# darlingtonDrivers.net
KiCad netlist of a schematic drawn in EAGLE
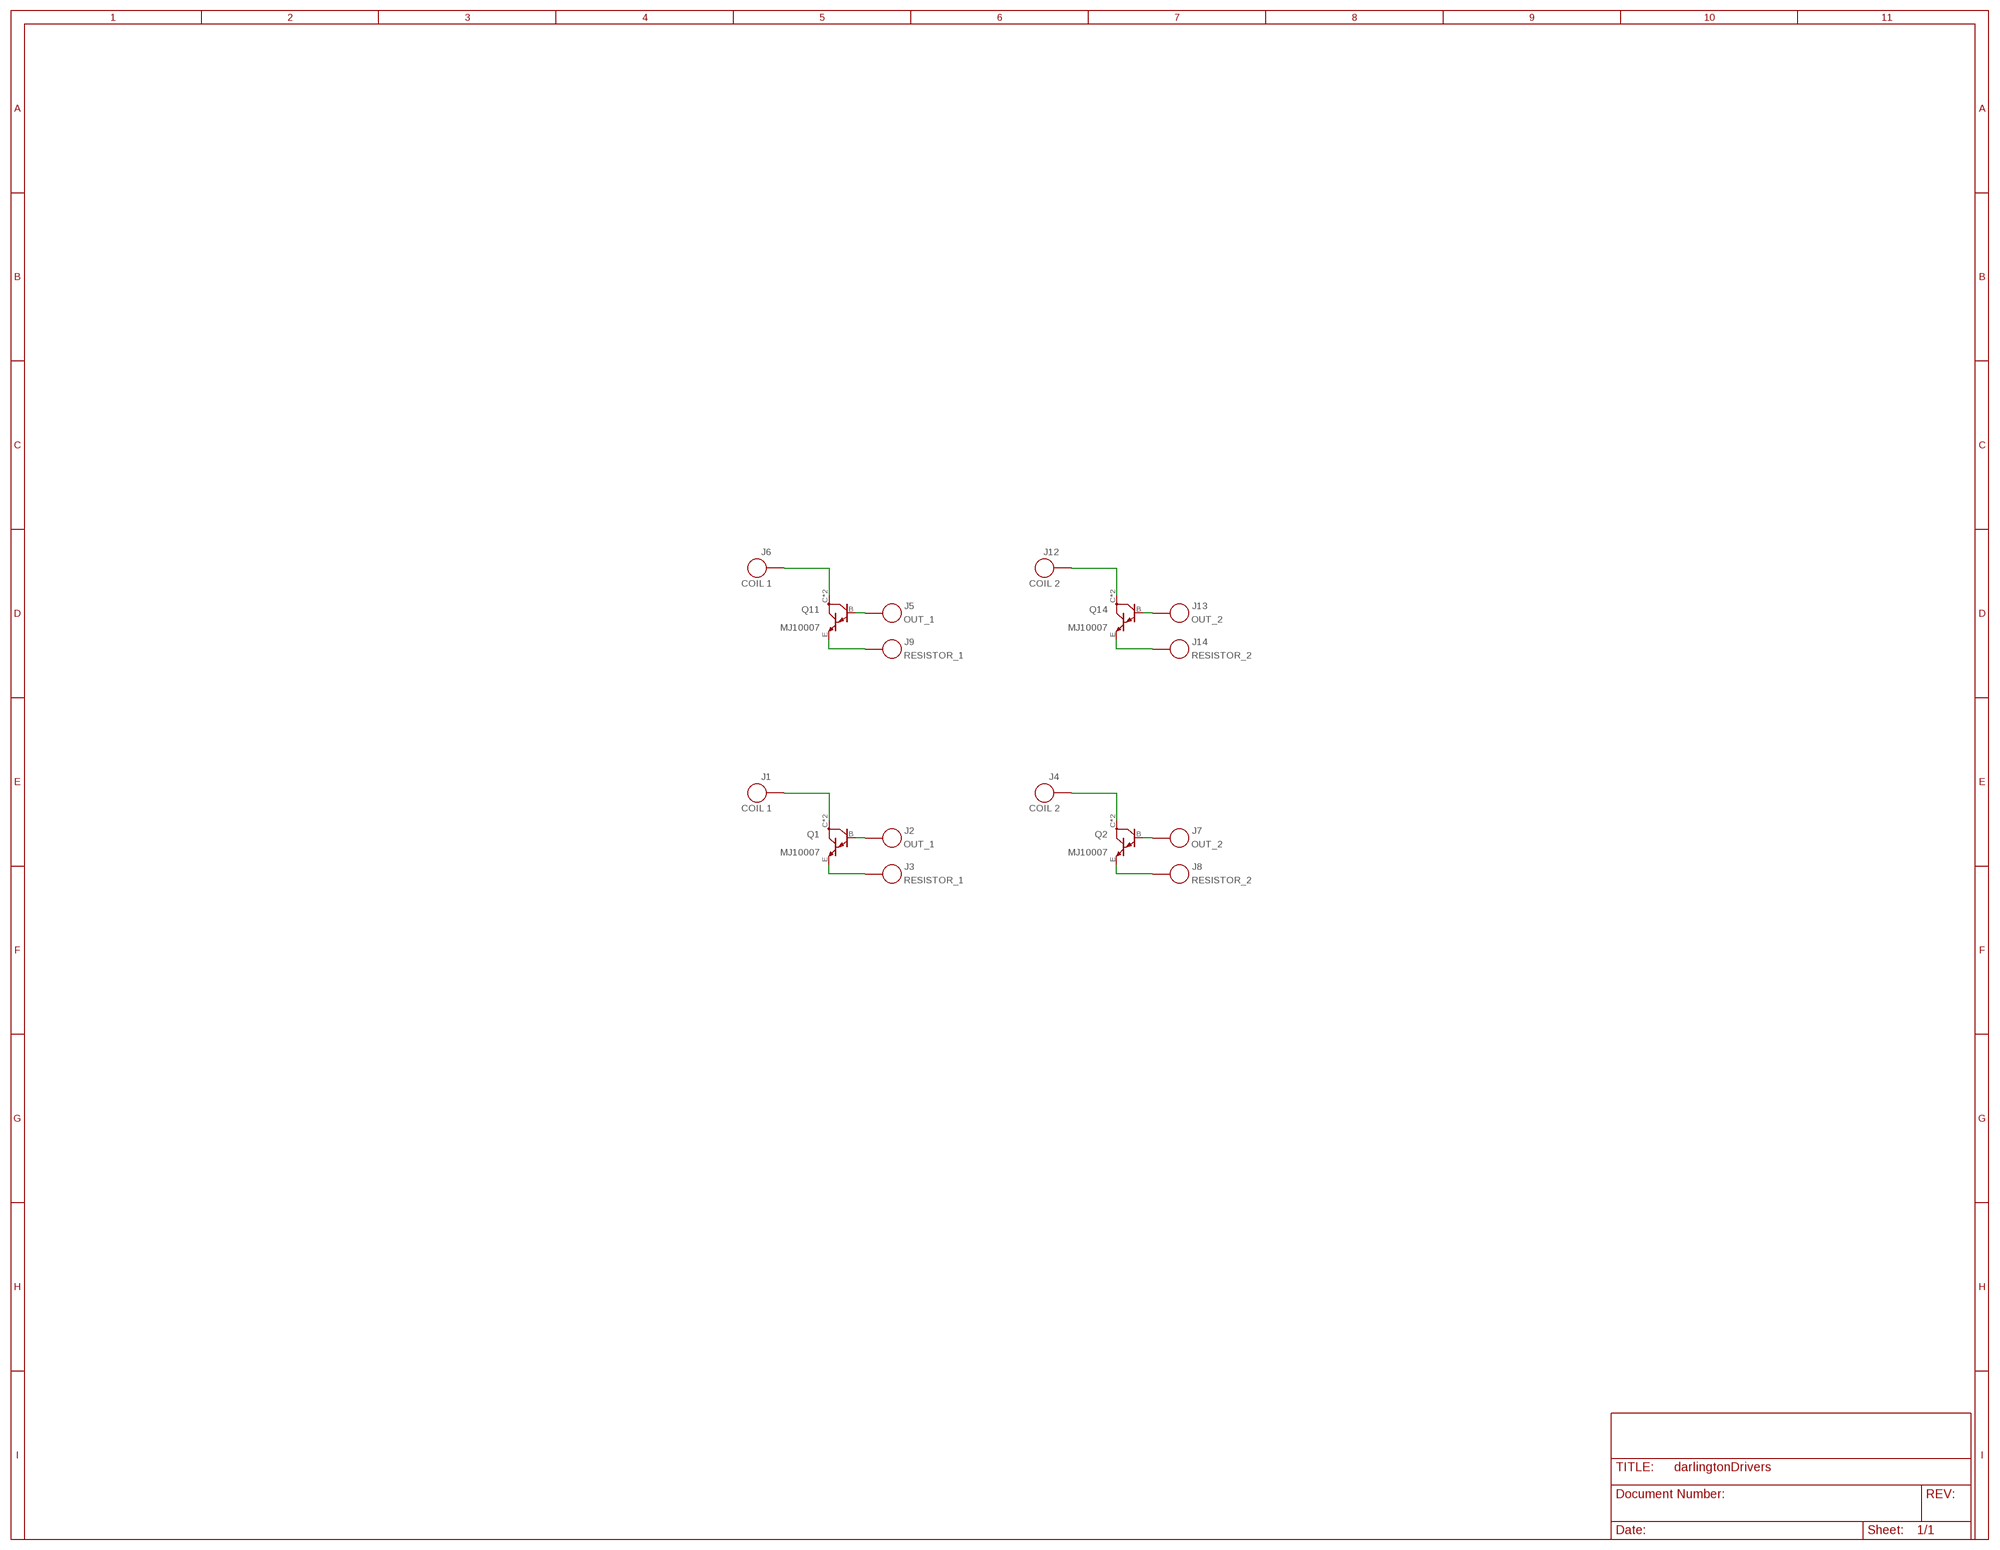
[diagram p0: schematic, sheet 1]

(export (version "E")
  (design (tool "Eeschema 10.0.6"))
  (components
    (comp (ref "J1")
      (value "COIL 1")
      (footprint "eagle-import:AWG18")
      (libsource (lib "eagle-import") (part "AWG18"))
    )
    (comp (ref "J2")
      (value "OUT_1")
      (footprint "eagle-import:AWG18")
      (libsource (lib "eagle-import") (part "AWG18"))
    )
    (comp (ref "J3")
      (value "RESISTOR_1")
      (footprint "eagle-import:AWG18")
      (libsource (lib "eagle-import") (part "AWG18"))
    )
    (comp (ref "J4")
      (value "COIL 2")
      (footprint "eagle-import:AWG18")
      (libsource (lib "eagle-import") (part "AWG18"))
    )
    (comp (ref "J5")
      (value "OUT_1")
      (footprint "eagle-import:AWG18")
      (libsource (lib "eagle-import") (part "AWG18"))
    )
    (comp (ref "J6")
      (value "COIL 1")
      (footprint "eagle-import:AWG18")
      (libsource (lib "eagle-import") (part "AWG18"))
    )
    (comp (ref "J7")
      (value "OUT_2")
      (footprint "eagle-import:AWG18")
      (libsource (lib "eagle-import") (part "AWG18"))
    )
    (comp (ref "J8")
      (value "RESISTOR_2")
      (footprint "eagle-import:AWG18")
      (libsource (lib "eagle-import") (part "AWG18"))
    )
    (comp (ref "J9")
      (value "RESISTOR_1")
      (footprint "eagle-import:AWG18")
      (libsource (lib "eagle-import") (part "AWG18"))
    )
    (comp (ref "J12")
      (value "COIL 2")
      (footprint "eagle-import:AWG18")
      (libsource (lib "eagle-import") (part "AWG18"))
    )
    (comp (ref "J13")
      (value "OUT_2")
      (footprint "eagle-import:AWG18")
      (libsource (lib "eagle-import") (part "AWG18"))
    )
    (comp (ref "J14")
      (value "RESISTOR_2")
      (footprint "eagle-import:AWG18")
      (libsource (lib "eagle-import") (part "AWG18"))
    )
    (comp (ref "Q1")
      (value "MJ10007")
      (footprint "eagle-import:TO3")
      (libsource (lib "eagle-import") (part "MJ10007"))
    )
    (comp (ref "Q2")
      (value "MJ10007")
      (footprint "eagle-import:TO3")
      (libsource (lib "eagle-import") (part "MJ10007"))
    )
    (comp (ref "Q11")
      (value "MJ10007")
      (footprint "eagle-import:TO3")
      (libsource (lib "eagle-import") (part "MJ10007"))
    )
    (comp (ref "Q14")
      (value "MJ10007")
      (footprint "eagle-import:TO3")
      (libsource (lib "eagle-import") (part "MJ10007"))
    )
  )
  (nets
    (net (code "1") (name "Net-(J1-PadP$1)") (class "Default")
      (node (ref "J1") (pin "P$1") (pinfunction "P$1_P$1") (pintype "bidirectional"))
      (node (ref "Q1") (pin "C") (pinfunction "C_C") (pintype "passive"))
      (node (ref "Q1") (pin "C/") (pinfunction "C_C/") (pintype "passive"))
    )
    (net (code "2") (name "Net-(J2-PadP$1)") (class "Default")
      (node (ref "J2") (pin "P$1") (pinfunction "P$1_P$1") (pintype "bidirectional"))
      (node (ref "Q1") (pin "B") (pinfunction "B_B") (pintype "passive"))
    )
    (net (code "3") (name "Net-(J3-PadP$1)") (class "Default")
      (node (ref "J3") (pin "P$1") (pinfunction "P$1_P$1") (pintype "bidirectional"))
      (node (ref "Q1") (pin "E") (pinfunction "E_E") (pintype "passive"))
    )
    (net (code "4") (name "Net-(J4-PadP$1)") (class "Default")
      (node (ref "J4") (pin "P$1") (pinfunction "P$1_P$1") (pintype "bidirectional"))
      (node (ref "Q2") (pin "C") (pinfunction "C_C") (pintype "passive"))
      (node (ref "Q2") (pin "C/") (pinfunction "C_C/") (pintype "passive"))
    )
    (net (code "5") (name "Net-(J5-PadP$1)") (class "Default")
      (node (ref "J5") (pin "P$1") (pinfunction "P$1_P$1") (pintype "bidirectional"))
      (node (ref "Q11") (pin "B") (pinfunction "B_B") (pintype "passive"))
    )
    (net (code "6") (name "Net-(J6-PadP$1)") (class "Default")
      (node (ref "J6") (pin "P$1") (pinfunction "P$1_P$1") (pintype "bidirectional"))
      (node (ref "Q11") (pin "C") (pinfunction "C_C") (pintype "passive"))
      (node (ref "Q11") (pin "C/") (pinfunction "C_C/") (pintype "passive"))
    )
    (net (code "7") (name "Net-(J7-PadP$1)") (class "Default")
      (node (ref "J7") (pin "P$1") (pinfunction "P$1_P$1") (pintype "bidirectional"))
      (node (ref "Q2") (pin "B") (pinfunction "B_B") (pintype "passive"))
    )
    (net (code "8") (name "Net-(J8-PadP$1)") (class "Default")
      (node (ref "J8") (pin "P$1") (pinfunction "P$1_P$1") (pintype "bidirectional"))
      (node (ref "Q2") (pin "E") (pinfunction "E_E") (pintype "passive"))
    )
    (net (code "9") (name "Net-(J9-PadP$1)") (class "Default")
      (node (ref "J9") (pin "P$1") (pinfunction "P$1_P$1") (pintype "bidirectional"))
      (node (ref "Q11") (pin "E") (pinfunction "E_E") (pintype "passive"))
    )
    (net (code "10") (name "Net-(J12-PadP$1)") (class "Default")
      (node (ref "J12") (pin "P$1") (pinfunction "P$1_P$1") (pintype "bidirectional"))
      (node (ref "Q14") (pin "C") (pinfunction "C_C") (pintype "passive"))
      (node (ref "Q14") (pin "C/") (pinfunction "C_C/") (pintype "passive"))
    )
    (net (code "11") (name "Net-(J13-PadP$1)") (class "Default")
      (node (ref "J13") (pin "P$1") (pinfunction "P$1_P$1") (pintype "bidirectional"))
      (node (ref "Q14") (pin "B") (pinfunction "B_B") (pintype "passive"))
    )
    (net (code "12") (name "Net-(J14-PadP$1)") (class "Default")
      (node (ref "J14") (pin "P$1") (pinfunction "P$1_P$1") (pintype "bidirectional"))
      (node (ref "Q14") (pin "E") (pinfunction "E_E") (pintype "passive"))
    )
  )
)
